# Peripheral.net
KiCad netlist of a schematic drawn in Altium Designer
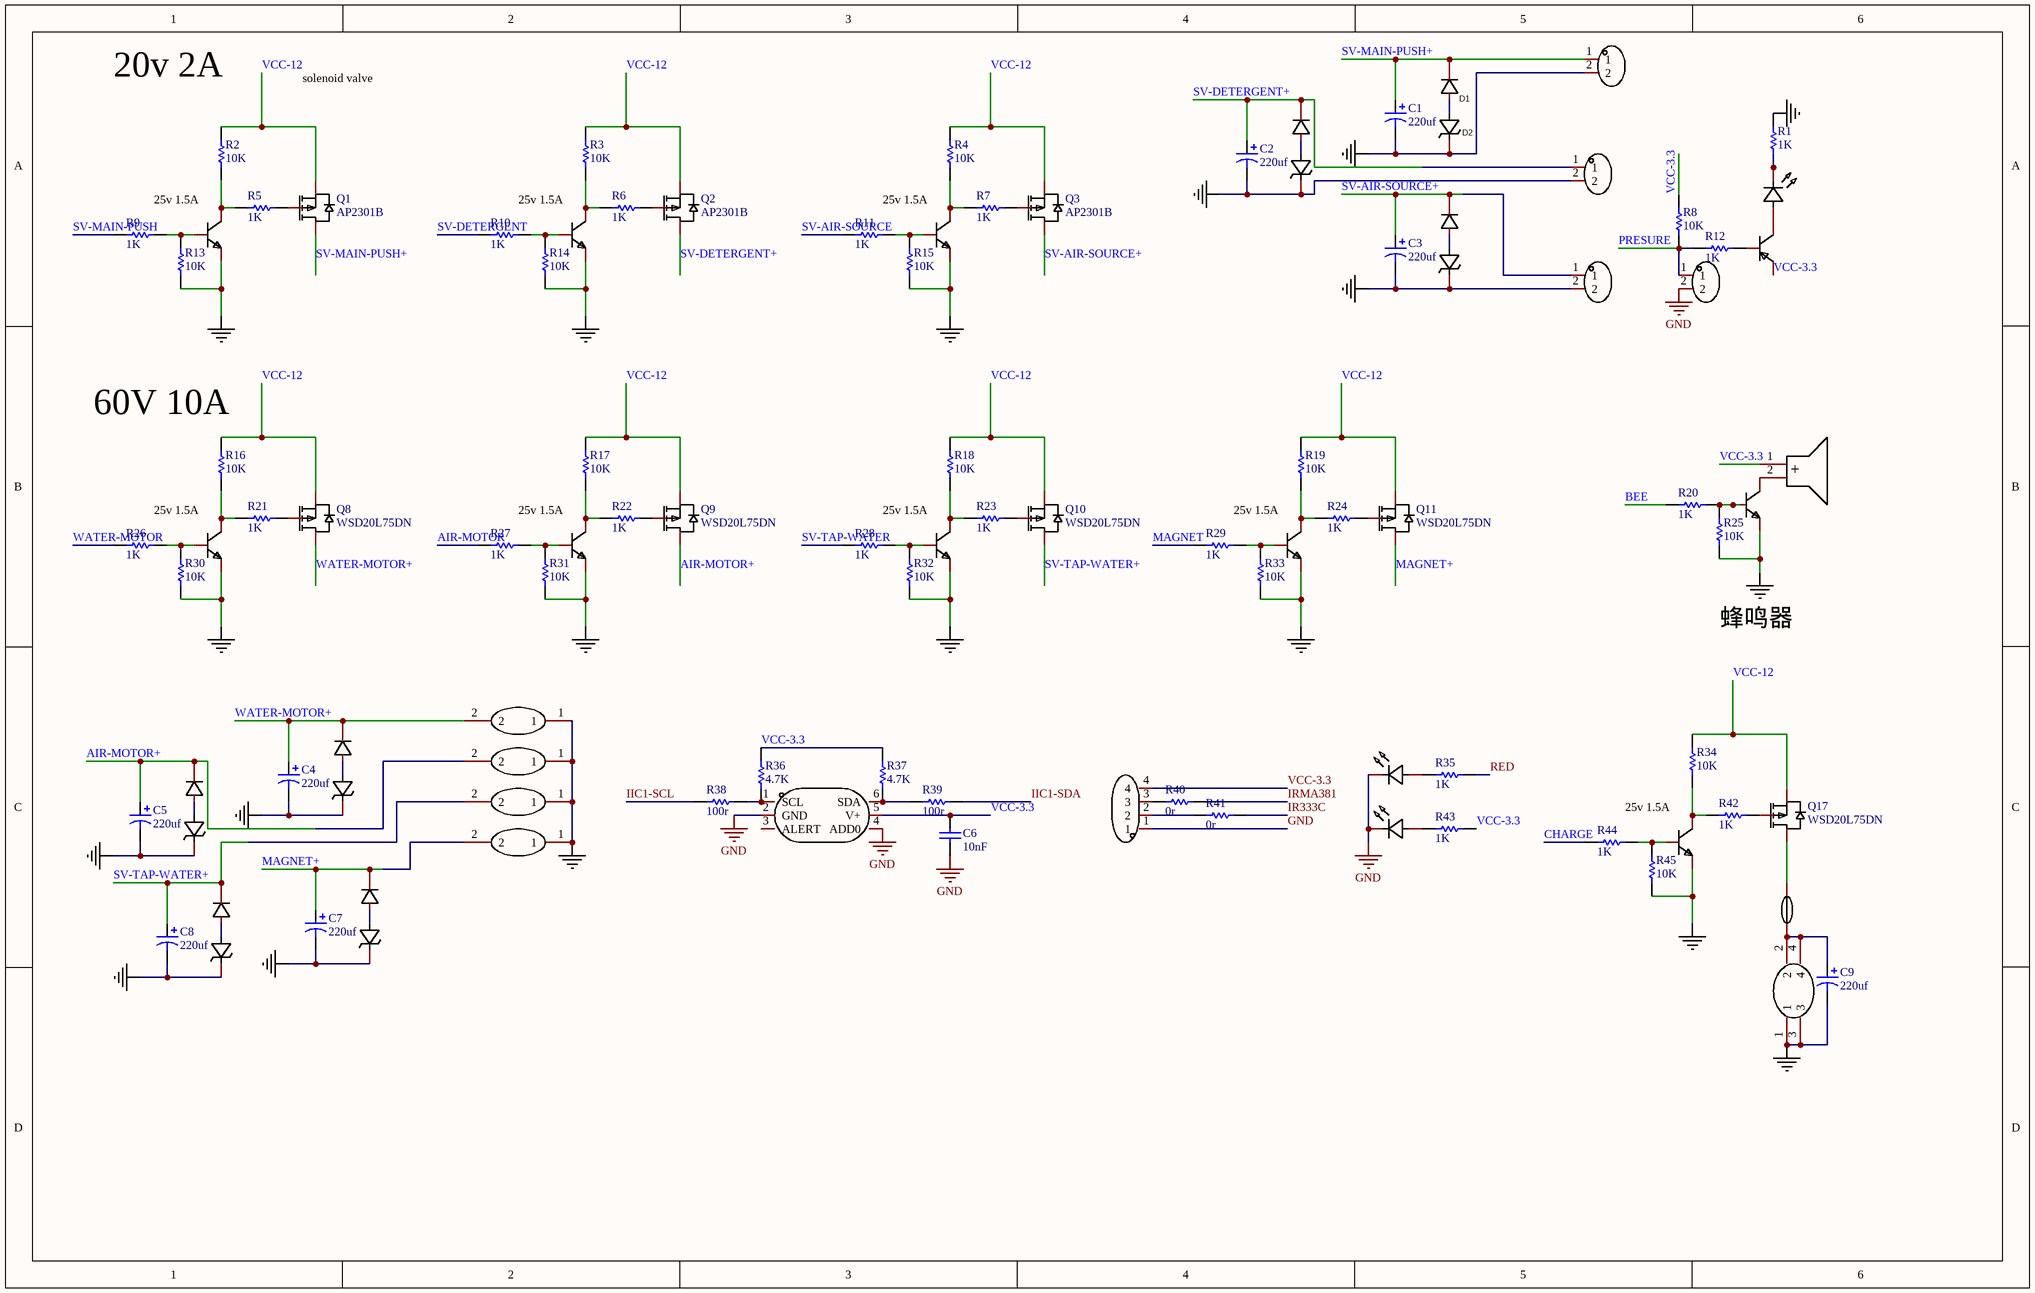
[diagram p0: Peripheral.SchDoc]

(export (version "E")
  (design (tool "Eeschema 10.0.6"))
  (components
    (comp (ref "B1")
      (value "HNB09A03")
      (footprint "BUZ-TH_BD9.0-P5.00-D0.6-FD")
      (fields (field (name "MANUFACTURER") "华能"))
      (libsource (lib "zq") (part "蜂鸣器（有源）"))
    )
    (comp (ref "C1")
      (value "220uf")
      (footprint "zq:CAP-SMD_BD6.3-L6.6-W6.6-LS7.4-FD")
      (description "Polarized Capacitor (Axial)")
      (fields (field (name "Comment") "RVT1E221M0607") (field (name "PUBLISHER") "Altium Limited"))
      (libsource (lib "zq") (part "Cap电解电容"))
    )
    (comp (ref "C2")
      (value "220uf")
      (footprint "zq:CAP-SMD_BD6.3-L6.6-W6.6-LS7.4-FD")
      (description "Polarized Capacitor (Axial)")
      (fields (field (name "Comment") "RVT1E221M0607") (field (name "PUBLISHER") "Altium Limited"))
      (libsource (lib "zq") (part "Cap电解电容"))
    )
    (comp (ref "C3")
      (value "220uf")
      (footprint "zq:CAP-SMD_BD6.3-L6.6-W6.6-LS7.4-FD")
      (description "Polarized Capacitor (Axial)")
      (fields (field (name "Comment") "RVT1E221M0607") (field (name "PUBLISHER") "Altium Limited"))
      (libsource (lib "zq") (part "Cap电解电容"))
    )
    (comp (ref "C4")
      (value "220uf")
      (footprint "zq:CAP-SMD_BD6.3-L6.6-W6.6-LS7.4-FD")
      (description "Polarized Capacitor (Axial)")
      (fields (field (name "Comment") "RVT1E221M0607") (field (name "PUBLISHER") "Altium Limited"))
      (libsource (lib "zq") (part "Cap电解电容"))
    )
    (comp (ref "C5")
      (value "220uf")
      (footprint "zq:CAP-SMD_BD6.3-L6.6-W6.6-LS7.4-FD")
      (description "Polarized Capacitor (Axial)")
      (fields (field (name "Comment") "RVT1E221M0607") (field (name "PUBLISHER") "Altium Limited"))
      (libsource (lib "zq") (part "Cap电解电容"))
    )
    (comp (ref "C6")
      (value "10nF")
      (footprint "zq:C0402")
      (description "Capacitor")
      (fields (field (name "Comment") "CL05B103KB5NNNC") (field (name "PUBLISHER") "Altium Limited"))
      (libsource (lib "zq") (part "10nf"))
    )
    (comp (ref "C7")
      (value "220uf")
      (footprint "zq:CAP-SMD_BD6.3-L6.6-W6.6-LS7.4-FD")
      (description "Polarized Capacitor (Axial)")
      (fields (field (name "Comment") "RVT1E221M0607") (field (name "PUBLISHER") "Altium Limited"))
      (libsource (lib "zq") (part "Cap电解电容"))
    )
    (comp (ref "C8")
      (value "220uf")
      (footprint "zq:CAP-SMD_BD6.3-L6.6-W6.6-LS7.4-FD")
      (description "Polarized Capacitor (Axial)")
      (fields (field (name "Comment") "RVT1E221M0607") (field (name "PUBLISHER") "Altium Limited"))
      (libsource (lib "zq") (part "Cap电解电容"))
    )
    (comp (ref "C9")
      (value "220uf")
      (footprint "zq:CAP-SMD_BD6.3-L6.6-W6.6-LS7.4-FD")
      (description "Polarized Capacitor (Axial)")
      (fields (field (name "Comment") "RVT1E221M0607") (field (name "PUBLISHER") "Altium Limited"))
      (libsource (lib "zq") (part "Cap电解电容"))
    )
    (comp (ref "D1")
      (value "SM4007PL")
      (footprint "zq:SOD-123F_L2.8-W1.8-LS3.7-RD")
      (description "普通二极管 1kv1A")
      (fields (field (name "MANUFACTURER") "MDD(辰达半导体)"))
      (libsource (lib "zq") (part "Diode ordinary"))
    )
    (comp (ref "D2")
      (value "BZT52C18W")
      (footprint "SOD-123_L2.7-W1.6-LS3.8-RD")
      (description "稳压二极管18v 5mA（击穿以后还能恢复）")
      (fields (field (name "MANUFACTURER") "CBI(创基)"))
      (libsource (lib "zq") (part "Diode 18v Zener"))
    )
    (comp (ref "D3")
      (value "SM4007PL")
      (footprint "zq:SOD-123F_L2.8-W1.8-LS3.7-RD")
      (description "普通二极管 1kv1A")
      (fields (field (name "MANUFACTURER") "MDD(辰达半导体)"))
      (libsource (lib "zq") (part "Diode ordinary"))
    )
    (comp (ref "D4")
      (value "BZT52C18W")
      (footprint "SOD-123_L2.7-W1.6-LS3.8-RD")
      (description "稳压二极管18v 5mA（击穿以后还能恢复）")
      (fields (field (name "MANUFACTURER") "CBI(创基)"))
      (libsource (lib "zq") (part "Diode 18v Zener"))
    )
    (comp (ref "D5")
      (value "SM4007PL")
      (footprint "zq:SOD-123F_L2.8-W1.8-LS3.7-RD")
      (description "普通二极管 1kv1A")
      (fields (field (name "MANUFACTURER") "MDD(辰达半导体)"))
      (libsource (lib "zq") (part "Diode ordinary"))
    )
    (comp (ref "D6")
      (value "BZT52C18W")
      (footprint "SOD-123_L2.7-W1.6-LS3.8-RD")
      (description "稳压二极管18v 5mA（击穿以后还能恢复）")
      (fields (field (name "MANUFACTURER") "CBI(创基)"))
      (libsource (lib "zq") (part "Diode 18v Zener"))
    )
    (comp (ref "D7")
      (value "SM4007PL")
      (footprint "zq:SOD-123F_L2.8-W1.8-LS3.7-RD")
      (description "普通二极管 1kv1A")
      (fields (field (name "MANUFACTURER") "MDD(辰达半导体)"))
      (libsource (lib "zq") (part "Diode ordinary"))
    )
    (comp (ref "D8")
      (value "BZT52C18W")
      (footprint "SOD-123_L2.7-W1.6-LS3.8-RD")
      (description "稳压二极管18v 5mA（击穿以后还能恢复）")
      (fields (field (name "MANUFACTURER") "CBI(创基)"))
      (libsource (lib "zq") (part "Diode 18v Zener"))
    )
    (comp (ref "D9")
      (value "KT-0603R")
      (footprint "LED0603-RD_RED")
      (description "红 0603 2.3v")
      (fields
        (field (name "MANUFACTURER") "XINGLIGHT(成兴光)")
        (field (name "MANUFACTURER PART") "XL-1608SURC-06")
      )
      (libsource (lib "zq") (part "led_R"))
    )
    (comp (ref "D10")
      (value "SM4007PL")
      (footprint "zq:SOD-123F_L2.8-W1.8-LS3.7-RD")
      (description "普通二极管 1kv1A")
      (fields (field (name "MANUFACTURER") "MDD(辰达半导体)"))
      (libsource (lib "zq") (part "Diode ordinary"))
    )
    (comp (ref "D11")
      (value "BZT52C18W")
      (footprint "SOD-123_L2.7-W1.6-LS3.8-RD")
      (description "稳压二极管18v 5mA（击穿以后还能恢复）")
      (fields (field (name "MANUFACTURER") "CBI(创基)"))
      (libsource (lib "zq") (part "Diode 18v Zener"))
    )
    (comp (ref "D12")
      (value "KT-0603W")
      (footprint "LED0603-RD_RED")
      (description "白 0603 2.3v")
      (fields
        (field (name "MANUFACTURER") "XINGLIGHT(成兴光)")
        (field (name "MANUFACTURER PART") "XL-1608SURC-06")
      )
      (libsource (lib "zq") (part "led_w"))
    )
    (comp (ref "D13")
      (value "SM4007PL")
      (footprint "zq:SOD-123F_L2.8-W1.8-LS3.7-RD")
      (description "普通二极管 1kv1A")
      (fields (field (name "MANUFACTURER") "MDD(辰达半导体)"))
      (libsource (lib "zq") (part "Diode ordinary"))
    )
    (comp (ref "D14")
      (value "SM4007PL")
      (footprint "zq:SOD-123F_L2.8-W1.8-LS3.7-RD")
      (description "普通二极管 1kv1A")
      (fields (field (name "MANUFACTURER") "MDD(辰达半导体)"))
      (libsource (lib "zq") (part "Diode ordinary"))
    )
    (comp (ref "D15")
      (value "BZT52C18W")
      (footprint "SOD-123_L2.7-W1.6-LS3.8-RD")
      (description "稳压二极管18v 5mA（击穿以后还能恢复）")
      (fields (field (name "MANUFACTURER") "CBI(创基)"))
      (libsource (lib "zq") (part "Diode 18v Zener"))
    )
    (comp (ref "D16")
      (value "BZT52C18W")
      (footprint "SOD-123_L2.7-W1.6-LS3.8-RD")
      (description "稳压二极管18v 5mA（击穿以后还能恢复）")
      (fields (field (name "MANUFACTURER") "CBI(创基)"))
      (libsource (lib "zq") (part "Diode 18v Zener"))
    )
    (comp (ref "F1")
      (value "BSMD2920-600-16V")
      (footprint "F2920")
      (description "自恢复保险丝 6A 16V")
      (fields (field (name "MANUFACTURER") "BHFUSE(佰宏)"))
      (libsource (lib "zq") (part "保险丝"))
    )
    (comp (ref "LED1")
      (value "19-213/Y2C-CQ2R2L/3T(CY)")
      (footprint "LED0603-RD_RED")
      (description "黄 0603 2.3v")
      (fields
        (field (name "MANUFACTURER") "XINGLIGHT(成兴光)")
        (field (name "MANUFACTURER PART") "XL-1608SURC-06")
      )
      (libsource (lib "zq") (part "led_y"))
    )
    (comp (ref "P1")
      (value "ZX-HY2.0-2PZZ")
      (footprint "zq:CONN-TH_2P-P2.00_ZX-HY2.0-2PZZ")
      (description "2p")
      (fields (field (name "MANUFACTURER") "Megastar(兆星)"))
      (libsource (lib "zq") (part "HY2.0-2PZZ"))
    )
    (comp (ref "P2")
      (value "ZX-HY2.0-2PZZ")
      (footprint "zq:CONN-TH_2P-P2.00_ZX-HY2.0-2PZZ")
      (description "2p")
      (fields (field (name "MANUFACTURER") "Megastar(兆星)"))
      (libsource (lib "zq") (part "HY2.0-2PZZ"))
    )
    (comp (ref "P3")
      (value "ZX-HY2.0-2PZZ")
      (footprint "zq:CONN-TH_2P-P2.00_ZX-HY2.0-2PZZ")
      (description "2p")
      (fields (field (name "MANUFACTURER") "Megastar(兆星)"))
      (libsource (lib "zq") (part "HY2.0-2PZZ"))
    )
    (comp (ref "P4")
      (value "ZX-HY2.0-2PZZ")
      (footprint "zq:CONN-TH_2P-P2.00_ZX-HY2.0-2PZZ")
      (description "2p")
      (fields (field (name "MANUFACTURER") "Megastar(兆星)"))
      (libsource (lib "zq") (part "HY2.0-2PZZ"))
    )
    (comp (ref "P5")
      (value "HC-5557-2*1A")
      (footprint "zq:CONN-TH_HAA420A-2A")
      (description "2p")
      (fields (field (name "MANUFACTURER") "HCTL(华灿天禄)"))
      (libsource (lib "zq") (part "HC-5557-2*1A"))
    )
    (comp (ref "P6")
      (value "HC-5557-2*1A")
      (footprint "zq:CONN-TH_HAA420A-2A")
      (description "2p")
      (fields (field (name "MANUFACTURER") "HCTL(华灿天禄)"))
      (libsource (lib "zq") (part "HC-5557-2*1A"))
    )
    (comp (ref "P7")
      (value "HC-5557-2*1A")
      (footprint "zq:CONN-TH_HAA420A-2A")
      (description "2p")
      (fields (field (name "MANUFACTURER") "HCTL(华灿天禄)"))
      (libsource (lib "zq") (part "HC-5557-2*1A"))
    )
    (comp (ref "P8")
      (value "ZX-HY2.0-4PZZ")
      (footprint "zq:CONN-TH_4P-P2.00_HX20020-4A_2")
      (description "4p")
      (fields (field (name "MANUFACTURER") "Megastar(兆星)"))
      (libsource (lib "zq") (part "HY2.0-4PZZ"))
    )
    (comp (ref "P9")
      (value "HC-5557-2*1A")
      (footprint "zq:CONN-TH_HAA420A-2A")
      (description "2p")
      (fields (field (name "MANUFACTURER") "HCTL(华灿天禄)"))
      (libsource (lib "zq") (part "HC-5557-2*1A"))
    )
    (comp (ref "P10")
      (value "HC-5557-2*2A")
      (footprint "zq:CONN-TH_HAA420A-4A")
      (description "4p")
      (fields (field (name "MANUFACTURER") "HCTL(华灿天禄)"))
      (libsource (lib "zq") (part "HC-5557-2*2A"))
    )
    (comp (ref "Q1")
      (value "AP2301B")
      (footprint "zq:SOT-23-3_L2.9-W1.3-P1.90-LS2.4-TR")
      (description "20V 2A")
      (fields (field (name "MANUFACTURER") "ALLPOWER(铨力)") (field (name "NAME") "AP2301B"))
      (libsource (lib "zq") (part "NPN_MOS"))
    )
    (comp (ref "Q2")
      (value "AP2301B")
      (footprint "zq:SOT-23-3_L2.9-W1.3-P1.90-LS2.4-TR")
      (description "20V 2A")
      (fields (field (name "MANUFACTURER") "ALLPOWER(铨力)") (field (name "NAME") "AP2301B"))
      (libsource (lib "zq") (part "NPN_MOS"))
    )
    (comp (ref "Q3")
      (value "AP2301B")
      (footprint "zq:SOT-23-3_L2.9-W1.3-P1.90-LS2.4-TR")
      (description "20V 2A")
      (fields (field (name "MANUFACTURER") "ALLPOWER(铨力)") (field (name "NAME") "AP2301B"))
      (libsource (lib "zq") (part "NPN_MOS"))
    )
    (comp (ref "Q4")
      (value "SS8050(RANGE:200-350)")
      (footprint "zq:SOT-23_L2.9-W1.3-P1.90-LS2.4-BR")
      (description "NPN三极管 高电平导通")
      (fields (field (name "MANUFACTURER") "Nexperia(安世)") (field (name "MANUFACTURER PART") "PMBT3904,215"))
      (libsource (lib "zq") (part "npn_triode"))
    )
    (comp (ref "Q5")
      (value "SS8050(RANGE:200-350)")
      (footprint "zq:SOT-23_L2.9-W1.3-P1.90-LS2.4-BR")
      (description "NPN三极管 高电平导通")
      (fields (field (name "MANUFACTURER") "Nexperia(安世)") (field (name "MANUFACTURER PART") "PMBT3904,215"))
      (libsource (lib "zq") (part "npn_triode"))
    )
    (comp (ref "Q6")
      (value "SS8050(RANGE:200-350)")
      (footprint "zq:SOT-23_L2.9-W1.3-P1.90-LS2.4-BR")
      (description "NPN三极管 高电平导通")
      (fields (field (name "MANUFACTURER") "Nexperia(安世)") (field (name "MANUFACTURER PART") "PMBT3904,215"))
      (libsource (lib "zq") (part "npn_triode"))
    )
    (comp (ref "Q7")
      (value "SS8550 Y2(RANGE:200-350)")
      (footprint "zq:SOT-23_L2.9-W1.3-P1.90-LS2.4-BR")
      (description "PNP三极管 低电平导通")
      (fields (field (name "MANUFACTURER") "CJ(江苏长电/长晶)") (field (name "MANUFACTURER PART") "SS8550 Y2"))
      (libsource (lib "zq") (part "pnp_triode"))
    )
    (comp (ref "Q8")
      (value "WSD20L75DN")
      (footprint "zq:DFN-8_L3.3-W3.3-P0.65-BL_WSD20L75DN")
      (description "20V 2A")
      (fields
        (field (name "MANUFACTURER") "ALLPOWER(铨力)")
        (field (name "MANUFACTURER PART") "AP2301B")
        (field (name "NAME") "WSD20L75DN")
      )
      (libsource (lib "zq") (part "NPN_MOS"))
    )
    (comp (ref "Q9")
      (value "WSD20L75DN")
      (footprint "zq:DFN-8_L3.3-W3.3-P0.65-BL_WSD20L75DN")
      (description "20V 2A")
      (fields
        (field (name "MANUFACTURER") "ALLPOWER(铨力)")
        (field (name "MANUFACTURER PART") "AP2301B")
        (field (name "NAME") "WSD20L75DN")
      )
      (libsource (lib "zq") (part "NPN_MOS"))
    )
    (comp (ref "Q10")
      (value "WSD20L75DN")
      (footprint "zq:DFN-8_L3.3-W3.3-P0.65-BL_WSD20L75DN")
      (description "20V 2A")
      (fields
        (field (name "MANUFACTURER") "ALLPOWER(铨力)")
        (field (name "MANUFACTURER PART") "AP2301B")
        (field (name "NAME") "WSD20L75DN")
      )
      (libsource (lib "zq") (part "NPN_MOS"))
    )
    (comp (ref "Q11")
      (value "WSD20L75DN")
      (footprint "zq:DFN-8_L3.3-W3.3-P0.65-BL_WSD20L75DN")
      (description "20V 2A")
      (fields
        (field (name "MANUFACTURER") "ALLPOWER(铨力)")
        (field (name "MANUFACTURER PART") "AP2301B")
        (field (name "NAME") "WSD20L75DN")
      )
      (libsource (lib "zq") (part "NPN_MOS"))
    )
    (comp (ref "Q12")
      (value "SS8050(RANGE:200-350)")
      (footprint "zq:SOT-23_L2.9-W1.3-P1.90-LS2.4-BR")
      (description "NPN三极管 高电平导通")
      (fields (field (name "MANUFACTURER") "Nexperia(安世)") (field (name "MANUFACTURER PART") "PMBT3904,215"))
      (libsource (lib "zq") (part "npn_triode"))
    )
    (comp (ref "Q13")
      (value "SS8050(RANGE:200-350)")
      (footprint "zq:SOT-23_L2.9-W1.3-P1.90-LS2.4-BR")
      (description "NPN三极管 高电平导通")
      (fields (field (name "MANUFACTURER") "Nexperia(安世)") (field (name "MANUFACTURER PART") "PMBT3904,215"))
      (libsource (lib "zq") (part "npn_triode"))
    )
    (comp (ref "Q14")
      (value "SS8050(RANGE:200-350)")
      (footprint "zq:SOT-23_L2.9-W1.3-P1.90-LS2.4-BR")
      (description "NPN三极管 高电平导通")
      (fields (field (name "MANUFACTURER") "Nexperia(安世)") (field (name "MANUFACTURER PART") "PMBT3904,215"))
      (libsource (lib "zq") (part "npn_triode"))
    )
    (comp (ref "Q15")
      (value "SS8050(RANGE:200-350)")
      (footprint "zq:SOT-23_L2.9-W1.3-P1.90-LS2.4-BR")
      (description "NPN三极管 高电平导通")
      (fields (field (name "MANUFACTURER") "Nexperia(安世)") (field (name "MANUFACTURER PART") "PMBT3904,215"))
      (libsource (lib "zq") (part "npn_triode"))
    )
    (comp (ref "Q16")
      (value "SS8050(RANGE:200-350)")
      (footprint "zq:SOT-23_L2.9-W1.3-P1.90-LS2.4-BR")
      (description "NPN三极管 高电平导通")
      (fields (field (name "MANUFACTURER") "Nexperia(安世)") (field (name "MANUFACTURER PART") "PMBT3904,215"))
      (libsource (lib "zq") (part "npn_triode"))
    )
    (comp (ref "Q17")
      (value "WSD20L75DN")
      (footprint "zq:DFN-8_L3.3-W3.3-P0.65-BL_WSD20L75DN")
      (description "20V 2A")
      (fields
        (field (name "MANUFACTURER") "ALLPOWER(铨力)")
        (field (name "MANUFACTURER PART") "AP2301B")
        (field (name "NAME") "WSD20L75DN")
      )
      (libsource (lib "zq") (part "NPN_MOS"))
    )
    (comp (ref "Q18")
      (value "SS8050(RANGE:200-350)")
      (footprint "zq:SOT-23_L2.9-W1.3-P1.90-LS2.4-BR")
      (description "NPN三极管 高电平导通")
      (fields (field (name "MANUFACTURER") "Nexperia(安世)") (field (name "MANUFACTURER PART") "PMBT3904,215"))
      (libsource (lib "zq") (part "npn_triode"))
    )
    (comp (ref "R1")
      (value "1K")
      (footprint "zq:R0402")
      (description "Semiconductor Resistor")
      (fields (field (name "Comment") "0402WGF1001TCE") (field (name "PUBLISHER") "Altium Limited"))
      (libsource (lib "zq") (part "1k"))
    )
    (comp (ref "R2")
      (value "10K")
      (footprint "zq:R0402")
      (description "Semiconductor Resistor")
      (fields (field (name "Comment") "0402WGF1002TCE") (field (name "PUBLISHER") "Altium Limited"))
      (libsource (lib "zq") (part "10K"))
    )
    (comp (ref "R3")
      (value "10K")
      (footprint "zq:R0402")
      (description "Semiconductor Resistor")
      (fields (field (name "Comment") "0402WGF1002TCE") (field (name "PUBLISHER") "Altium Limited"))
      (libsource (lib "zq") (part "10K"))
    )
    (comp (ref "R4")
      (value "10K")
      (footprint "zq:R0402")
      (description "Semiconductor Resistor")
      (fields (field (name "Comment") "0402WGF1002TCE") (field (name "PUBLISHER") "Altium Limited"))
      (libsource (lib "zq") (part "10K"))
    )
    (comp (ref "R5")
      (value "1K")
      (footprint "zq:R0402")
      (description "Semiconductor Resistor")
      (fields (field (name "Comment") "0402WGF1001TCE") (field (name "PUBLISHER") "Altium Limited"))
      (libsource (lib "zq") (part "1k"))
    )
    (comp (ref "R6")
      (value "1K")
      (footprint "zq:R0402")
      (description "Semiconductor Resistor")
      (fields (field (name "Comment") "0402WGF1001TCE") (field (name "PUBLISHER") "Altium Limited"))
      (libsource (lib "zq") (part "1k"))
    )
    (comp (ref "R7")
      (value "1K")
      (footprint "zq:R0402")
      (description "Semiconductor Resistor")
      (fields (field (name "Comment") "0402WGF1001TCE") (field (name "PUBLISHER") "Altium Limited"))
      (libsource (lib "zq") (part "1k"))
    )
    (comp (ref "R8")
      (value "10K")
      (footprint "zq:R0402")
      (description "Semiconductor Resistor")
      (fields (field (name "Comment") "0402WGF1002TCE") (field (name "PUBLISHER") "Altium Limited"))
      (libsource (lib "zq") (part "10K"))
    )
    (comp (ref "R9")
      (value "1K")
      (footprint "zq:R0402")
      (description "Semiconductor Resistor")
      (fields (field (name "Comment") "0402WGF1001TCE") (field (name "PUBLISHER") "Altium Limited"))
      (libsource (lib "zq") (part "1k"))
    )
    (comp (ref "R10")
      (value "1K")
      (footprint "zq:R0402")
      (description "Semiconductor Resistor")
      (fields (field (name "Comment") "0402WGF1001TCE") (field (name "PUBLISHER") "Altium Limited"))
      (libsource (lib "zq") (part "1k"))
    )
    (comp (ref "R11")
      (value "1K")
      (footprint "zq:R0402")
      (description "Semiconductor Resistor")
      (fields (field (name "Comment") "0402WGF1001TCE") (field (name "PUBLISHER") "Altium Limited"))
      (libsource (lib "zq") (part "1k"))
    )
    (comp (ref "R12")
      (value "1K")
      (footprint "zq:R0402")
      (description "Semiconductor Resistor")
      (fields (field (name "Comment") "0402WGF1001TCE") (field (name "PUBLISHER") "Altium Limited"))
      (libsource (lib "zq") (part "1k"))
    )
    (comp (ref "R13")
      (value "10K")
      (footprint "zq:R0402")
      (description "Semiconductor Resistor")
      (fields (field (name "Comment") "0402WGF1002TCE") (field (name "PUBLISHER") "Altium Limited"))
      (libsource (lib "zq") (part "10K"))
    )
    (comp (ref "R14")
      (value "10K")
      (footprint "zq:R0402")
      (description "Semiconductor Resistor")
      (fields (field (name "Comment") "0402WGF1002TCE") (field (name "PUBLISHER") "Altium Limited"))
      (libsource (lib "zq") (part "10K"))
    )
    (comp (ref "R15")
      (value "10K")
      (footprint "zq:R0402")
      (description "Semiconductor Resistor")
      (fields (field (name "Comment") "0402WGF1002TCE") (field (name "PUBLISHER") "Altium Limited"))
      (libsource (lib "zq") (part "10K"))
    )
    (comp (ref "R16")
      (value "10K")
      (footprint "zq:R0402")
      (description "Semiconductor Resistor")
      (fields (field (name "Comment") "0402WGF1002TCE") (field (name "PUBLISHER") "Altium Limited"))
      (libsource (lib "zq") (part "10K"))
    )
    (comp (ref "R17")
      (value "10K")
      (footprint "zq:R0402")
      (description "Semiconductor Resistor")
      (fields (field (name "Comment") "0402WGF1002TCE") (field (name "PUBLISHER") "Altium Limited"))
      (libsource (lib "zq") (part "10K"))
    )
    (comp (ref "R18")
      (value "10K")
      (footprint "zq:R0402")
      (description "Semiconductor Resistor")
      (fields (field (name "Comment") "0402WGF1002TCE") (field (name "PUBLISHER") "Altium Limited"))
      (libsource (lib "zq") (part "10K"))
    )
    (comp (ref "R19")
      (value "10K")
      (footprint "zq:R0402")
      (description "Semiconductor Resistor")
      (fields (field (name "Comment") "0402WGF1002TCE") (field (name "PUBLISHER") "Altium Limited"))
      (libsource (lib "zq") (part "10K"))
    )
    (comp (ref "R20")
      (value "1K")
      (footprint "zq:R0402")
      (description "Semiconductor Resistor")
      (fields (field (name "Comment") "0402WGF1001TCE") (field (name "PUBLISHER") "Altium Limited"))
      (libsource (lib "zq") (part "1k"))
    )
    (comp (ref "R21")
      (value "1K")
      (footprint "zq:R0402")
      (description "Semiconductor Resistor")
      (fields (field (name "Comment") "0402WGF1001TCE") (field (name "PUBLISHER") "Altium Limited"))
      (libsource (lib "zq") (part "1k"))
    )
    (comp (ref "R22")
      (value "1K")
      (footprint "zq:R0402")
      (description "Semiconductor Resistor")
      (fields (field (name "Comment") "0402WGF1001TCE") (field (name "PUBLISHER") "Altium Limited"))
      (libsource (lib "zq") (part "1k"))
    )
    (comp (ref "R23")
      (value "1K")
      (footprint "zq:R0402")
      (description "Semiconductor Resistor")
      (fields (field (name "Comment") "0402WGF1001TCE") (field (name "PUBLISHER") "Altium Limited"))
      (libsource (lib "zq") (part "1k"))
    )
    (comp (ref "R24")
      (value "1K")
      (footprint "zq:R0402")
      (description "Semiconductor Resistor")
      (fields (field (name "Comment") "0402WGF1001TCE") (field (name "PUBLISHER") "Altium Limited"))
      (libsource (lib "zq") (part "1k"))
    )
    (comp (ref "R25")
      (value "10K")
      (footprint "zq:R0402")
      (description "Semiconductor Resistor")
      (fields (field (name "Comment") "0402WGF1002TCE") (field (name "PUBLISHER") "Altium Limited"))
      (libsource (lib "zq") (part "10K"))
    )
    (comp (ref "R26")
      (value "1K")
      (footprint "zq:R0402")
      (description "Semiconductor Resistor")
      (fields (field (name "Comment") "0402WGF1001TCE") (field (name "PUBLISHER") "Altium Limited"))
      (libsource (lib "zq") (part "1k"))
    )
    (comp (ref "R27")
      (value "1K")
      (footprint "zq:R0402")
      (description "Semiconductor Resistor")
      (fields (field (name "Comment") "0402WGF1001TCE") (field (name "PUBLISHER") "Altium Limited"))
      (libsource (lib "zq") (part "1k"))
    )
    (comp (ref "R28")
      (value "1K")
      (footprint "zq:R0402")
      (description "Semiconductor Resistor")
      (fields (field (name "Comment") "0402WGF1001TCE") (field (name "PUBLISHER") "Altium Limited"))
      (libsource (lib "zq") (part "1k"))
    )
    (comp (ref "R29")
      (value "1K")
      (footprint "zq:R0402")
      (description "Semiconductor Resistor")
      (fields (field (name "Comment") "0402WGF1001TCE") (field (name "PUBLISHER") "Altium Limited"))
      (libsource (lib "zq") (part "1k"))
    )
    (comp (ref "R30")
      (value "10K")
      (footprint "zq:R0402")
      (description "Semiconductor Resistor")
      (fields (field (name "Comment") "0402WGF1002TCE") (field (name "PUBLISHER") "Altium Limited"))
      (libsource (lib "zq") (part "10K"))
    )
    (comp (ref "R31")
      (value "10K")
      (footprint "zq:R0402")
      (description "Semiconductor Resistor")
      (fields (field (name "Comment") "0402WGF1002TCE") (field (name "PUBLISHER") "Altium Limited"))
      (libsource (lib "zq") (part "10K"))
    )
    (comp (ref "R32")
      (value "10K")
      (footprint "zq:R0402")
      (description "Semiconductor Resistor")
      (fields (field (name "Comment") "0402WGF1002TCE") (field (name "PUBLISHER") "Altium Limited"))
      (libsource (lib "zq") (part "10K"))
    )
    (comp (ref "R33")
      (value "10K")
      (footprint "zq:R0402")
      (description "Semiconductor Resistor")
      (fields (field (name "Comment") "0402WGF1002TCE") (field (name "PUBLISHER") "Altium Limited"))
      (libsource (lib "zq") (part "10K"))
    )
    (comp (ref "R34")
      (value "10K")
      (footprint "zq:R0402")
      (description "Semiconductor Resistor")
      (fields (field (name "Comment") "0402WGF1002TCE") (field (name "PUBLISHER") "Altium Limited"))
      (libsource (lib "zq") (part "10K"))
    )
    (comp (ref "R35")
      (value "1K")
      (footprint "zq:R0402")
      (description "Semiconductor Resistor")
      (fields (field (name "Comment") "0402WGF1001TCE") (field (name "PUBLISHER") "Altium Limited"))
      (libsource (lib "zq") (part "1k"))
    )
    (comp (ref "R36")
      (value "4.7K")
      (footprint "zq:R0402")
      (description "Semiconductor Resistor")
      (fields (field (name "Comment") "0402WGF4701TCE") (field (name "PUBLISHER") "Altium Limited"))
      (libsource (lib "zq") (part "4.7k"))
    )
    (comp (ref "R37")
      (value "4.7K")
      (footprint "zq:R0402")
      (description "Semiconductor Resistor")
      (fields (field (name "Comment") "0402WGF4701TCE") (field (name "PUBLISHER") "Altium Limited"))
      (libsource (lib "zq") (part "4.7k"))
    )
    (comp (ref "R38")
      (value "100r")
      (footprint "zq:R0402")
      (fields (field (name "Comment") "0402WGF1000TCE") (field (name "PUBLISHER") "Altium Limited"))
      (libsource (lib "zq") (part "100r"))
    )
    (comp (ref "R39")
      (value "100r")
      (footprint "zq:R0402")
      (fields (field (name "Comment") "0402WGF1000TCE") (field (name "PUBLISHER") "Altium Limited"))
      (libsource (lib "zq") (part "100r"))
    )
    (comp (ref "R40")
      (value "0r")
      (footprint "zq:R0402")
      (fields (field (name "Comment") "0402WGF0000TCE") (field (name "PUBLISHER") "Altium Limited"))
      (libsource (lib "zq") (part "0r"))
    )
    (comp (ref "R41")
      (value "0r")
      (footprint "zq:R0402")
      (fields (field (name "Comment") "0402WGF0000TCE") (field (name "PUBLISHER") "Altium Limited"))
      (libsource (lib "zq") (part "0r"))
    )
    (comp (ref "R42")
      (value "1K")
      (footprint "zq:R0402")
      (description "Semiconductor Resistor")
      (fields (field (name "Comment") "0402WGF1001TCE") (field (name "PUBLISHER") "Altium Limited"))
      (libsource (lib "zq") (part "1k"))
    )
    (comp (ref "R43")
      (value "1K")
      (footprint "zq:R0402")
      (description "Semiconductor Resistor")
      (fields (field (name "Comment") "0402WGF1001TCE") (field (name "PUBLISHER") "Altium Limited"))
      (libsource (lib "zq") (part "1k"))
    )
    (comp (ref "R44")
      (value "1K")
      (footprint "zq:R0402")
      (description "Semiconductor Resistor")
      (fields (field (name "Comment") "0402WGF1001TCE") (field (name "PUBLISHER") "Altium Limited"))
      (libsource (lib "zq") (part "1k"))
    )
    (comp (ref "R45")
      (value "10K")
      (footprint "zq:R0402")
      (description "Semiconductor Resistor")
      (fields (field (name "Comment") "0402WGF1002TCE") (field (name "PUBLISHER") "Altium Limited"))
      (libsource (lib "zq") (part "10K"))
    )
    (comp (ref "U1")
      (value "TMP112AIDRLR")
      (footprint "SOT-563_L1.6-W1.2-P0.50-LS1.6-BR")
      (description "温度传感器")
      (fields (field (name "MANUFACTURER") "UMW(友台半导体)"))
      (libsource (lib "zq") (part "TMP112AIDRLR"))
    )
  )
  (nets
    (net (code "1") (name "/AIR-MOTOR") (class "Default")
      (node (ref "R27") (pin "1") (pinfunction "1_1") (pintype "passive"))
    )
    (net (code "2") (name "/AIR-MOTOR+") (class "Default")
      (node (ref "C5") (pin "1") (pinfunction "1_1") (pintype "passive"))
      (node (ref "D10") (pin "1") (pinfunction "C_1") (pintype "passive"))
      (node (ref "P6") (pin "2") (pinfunction "2_2") (pintype "passive"))
      (node (ref "Q9") (pin "3") (pinfunction "D_3") (pintype "passive"))
    )
    (net (code "3") (name "/BEE") (class "Default")
      (node (ref "R20") (pin "1") (pinfunction "1_1") (pintype "passive"))
    )
    (net (code "4") (name "/CHARGE") (class "Default")
      (node (ref "R44") (pin "1") (pinfunction "1_1") (pintype "passive"))
    )
    (net (code "5") (name "/IIC1-SCL") (class "Default")
      (node (ref "R38") (pin "1") (pinfunction "1_1") (pintype "passive"))
    )
    (net (code "6") (name "/IIC1-SDA") (class "Default")
      (node (ref "R39") (pin "2") (pinfunction "2_2") (pintype "passive"))
    )
    (net (code "7") (name "/IR333C") (class "Default")
      (node (ref "R41") (pin "2") (pinfunction "2_2") (pintype "passive"))
    )
    (net (code "8") (name "/IRMA381") (class "Default")
      (node (ref "R40") (pin "2") (pinfunction "2_2") (pintype "passive"))
    )
    (net (code "9") (name "/MAGNET") (class "Default")
      (node (ref "R29") (pin "1") (pinfunction "1_1") (pintype "passive"))
    )
    (net (code "10") (name "/MAGNET+") (class "Default")
      (node (ref "C7") (pin "1") (pinfunction "1_1") (pintype "passive"))
      (node (ref "D13") (pin "1") (pinfunction "C_1") (pintype "passive"))
      (node (ref "P9") (pin "2") (pinfunction "2_2") (pintype "passive"))
      (node (ref "Q11") (pin "3") (pinfunction "D_3") (pintype "passive"))
    )
    (net (code "11") (name "/PRESURE") (class "Default")
      (node (ref "P4") (pin "1") (pinfunction "1_1") (pintype "passive"))
      (node (ref "R12") (pin "2") (pinfunction "2_2") (pintype "passive"))
      (node (ref "R8") (pin "1") (pinfunction "1_1") (pintype "passive"))
    )
    (net (code "12") (name "/RED") (class "Default")
      (node (ref "R35") (pin "2") (pinfunction "2_2") (pintype "passive"))
    )
    (net (code "13") (name "/SV-AIR-SOURCE") (class "Default")
      (node (ref "R11") (pin "1") (pinfunction "1_1") (pintype "passive"))
    )
    (net (code "14") (name "/SV-AIR-SOURCE+") (class "Default")
      (node (ref "C3") (pin "1") (pinfunction "1_1") (pintype "passive"))
      (node (ref "D5") (pin "1") (pinfunction "C_1") (pintype "passive"))
      (node (ref "P3") (pin "1") (pinfunction "1_1") (pintype "passive"))
      (node (ref "Q3") (pin "3") (pinfunction "D_3") (pintype "passive"))
    )
    (net (code "15") (name "/SV-DETERGENT") (class "Default")
      (node (ref "R10") (pin "1") (pinfunction "1_1") (pintype "passive"))
    )
    (net (code "16") (name "/SV-DETERGENT+") (class "Default")
      (node (ref "C2") (pin "1") (pinfunction "1_1") (pintype "passive"))
      (node (ref "D3") (pin "1") (pinfunction "C_1") (pintype "passive"))
      (node (ref "P2") (pin "1") (pinfunction "1_1") (pintype "passive"))
      (node (ref "Q2") (pin "3") (pinfunction "D_3") (pintype "passive"))
    )
    (net (code "17") (name "/SV-MAIN-PUSH") (class "Default")
      (node (ref "R9") (pin "1") (pinfunction "1_1") (pintype "passive"))
    )
    (net (code "18") (name "/SV-MAIN-PUSH+") (class "Default")
      (node (ref "C1") (pin "1") (pinfunction "1_1") (pintype "passive"))
      (node (ref "D1") (pin "1") (pinfunction "C_1") (pintype "passive"))
      (node (ref "P1") (pin "1") (pinfunction "1_1") (pintype "passive"))
      (node (ref "Q1") (pin "3") (pinfunction "D_3") (pintype "passive"))
    )
    (net (code "19") (name "/SV-TAP-WATER") (class "Default")
      (node (ref "R28") (pin "1") (pinfunction "1_1") (pintype "passive"))
    )
    (net (code "20") (name "/SV-TAP-WATER+") (class "Default")
      (node (ref "C8") (pin "1") (pinfunction "1_1") (pintype "passive"))
      (node (ref "D14") (pin "1") (pinfunction "C_1") (pintype "passive"))
      (node (ref "P7") (pin "2") (pinfunction "2_2") (pintype "passive"))
      (node (ref "Q10") (pin "3") (pinfunction "D_3") (pintype "passive"))
    )
    (net (code "21") (name "/VCC-3.3") (class "Default")
      (node (ref "B1") (pin "1") (pinfunction "+_1") (pintype "passive"))
      (node (ref "C6") (pin "1") (pinfunction "1_1") (pintype "passive"))
      (node (ref "P8") (pin "4") (pinfunction "4_4") (pintype "passive"))
      (node (ref "Q7") (pin "2") (pinfunction "E_2") (pintype "passive"))
      (node (ref "R36") (pin "2") (pinfunction "2_2") (pintype "passive"))
      (node (ref "R37") (pin "2") (pinfunction "2_2") (pintype "passive"))
      (node (ref "R43") (pin "2") (pinfunction "2_2") (pintype "passive"))
      (node (ref "R8") (pin "2") (pinfunction "2_2") (pintype "passive"))
      (node (ref "U1") (pin "5") (pinfunction "V+_5") (pintype "passive"))
    )
    (net (code "22") (name "/VCC-12") (class "Default")
      (node (ref "Q1") (pin "1") (pinfunction "S_1") (pintype "passive"))
      (node (ref "Q10") (pin "1") (pinfunction "S_1") (pintype "passive"))
      (node (ref "Q11") (pin "1") (pinfunction "S_1") (pintype "passive"))
      (node (ref "Q17") (pin "1") (pinfunction "S_1") (pintype "passive"))
      (node (ref "Q2") (pin "1") (pinfunction "S_1") (pintype "passive"))
      (node (ref "Q3") (pin "1") (pinfunction "S_1") (pintype "passive"))
      (node (ref "Q8") (pin "1") (pinfunction "S_1") (pintype "passive"))
      (node (ref "Q9") (pin "1") (pinfunction "S_1") (pintype "passive"))
      (node (ref "R16") (pin "2") (pinfunction "2_2") (pintype "passive"))
      (node (ref "R17") (pin "2") (pinfunction "2_2") (pintype "passive"))
      (node (ref "R18") (pin "2") (pinfunction "2_2") (pintype "passive"))
      (node (ref "R19") (pin "2") (pinfunction "2_2") (pintype "passive"))
      (node (ref "R2") (pin "2") (pinfunction "2_2") (pintype "passive"))
      (node (ref "R3") (pin "2") (pinfunction "2_2") (pintype "passive"))
      (node (ref "R34") (pin "2") (pinfunction "2_2") (pintype "passive"))
      (node (ref "R4") (pin "2") (pinfunction "2_2") (pintype "passive"))
    )
    (net (code "23") (name "/WATER-MOTOR") (class "Default")
      (node (ref "R26") (pin "1") (pinfunction "1_1") (pintype "passive"))
    )
    (net (code "24") (name "/WATER-MOTOR+") (class "Default")
      (node (ref "C4") (pin "1") (pinfunction "1_1") (pintype "passive"))
      (node (ref "D7") (pin "1") (pinfunction "C_1") (pintype "passive"))
      (node (ref "P5") (pin "2") (pinfunction "2_2") (pintype "passive"))
      (node (ref "Q8") (pin "3") (pinfunction "D_3") (pintype "passive"))
    )
    (net (code "25") (name "GND") (class "Default")
      (node (ref "C1") (pin "2") (pinfunction "2_2") (pintype "passive"))
      (node (ref "C2") (pin "2") (pinfunction "2_2") (pintype "passive"))
      (node (ref "C3") (pin "2") (pinfunction "2_2") (pintype "passive"))
      (node (ref "C4") (pin "2") (pinfunction "2_2") (pintype "passive"))
      (node (ref "C5") (pin "2") (pinfunction "2_2") (pintype "passive"))
      (node (ref "C6") (pin "2") (pinfunction "2_2") (pintype "passive"))
      (node (ref "C7") (pin "2") (pinfunction "2_2") (pintype "passive"))
      (node (ref "C8") (pin "2") (pinfunction "2_2") (pintype "passive"))
      (node (ref "C9") (pin "2") (pinfunction "2_2") (pintype "passive"))
      (node (ref "D11") (pin "1") (pinfunction "C_1") (pintype "passive"))
      (node (ref "D12") (pin "1") (pinfunction "K_1") (pintype "passive"))
      (node (ref "D15") (pin "1") (pinfunction "C_1") (pintype "passive"))
      (node (ref "D16") (pin "1") (pinfunction "C_1") (pintype "passive"))
      (node (ref "D2") (pin "1") (pinfunction "C_1") (pintype "passive"))
      (node (ref "D4") (pin "1") (pinfunction "C_1") (pintype "passive"))
      (node (ref "D6") (pin "1") (pinfunction "C_1") (pintype "passive"))
      (node (ref "D8") (pin "1") (pinfunction "C_1") (pintype "passive"))
      (node (ref "D9") (pin "1") (pinfunction "K_1") (pintype "passive"))
      (node (ref "P1") (pin "2") (pinfunction "2_2") (pintype "passive"))
      (node (ref "P10") (pin "1") (pinfunction "1_1") (pintype "passive"))
      (node (ref "P10") (pin "3") (pinfunction "3_3") (pintype "passive"))
      (node (ref "P2") (pin "2") (pinfunction "2_2") (pintype "passive"))
      (node (ref "P3") (pin "2") (pinfunction "2_2") (pintype "passive"))
      (node (ref "P4") (pin "2") (pinfunction "2_2") (pintype "passive"))
      (node (ref "P5") (pin "1") (pinfunction "1_1") (pintype "passive"))
      (node (ref "P6") (pin "1") (pinfunction "1_1") (pintype "passive"))
      (node (ref "P7") (pin "1") (pinfunction "1_1") (pintype "passive"))
      (node (ref "P8") (pin "1") (pinfunction "1_1") (pintype "passive"))
      (node (ref "P9") (pin "1") (pinfunction "1_1") (pintype "passive"))
      (node (ref "Q12") (pin "2") (pinfunction "2_2") (pintype "passive"))
      (node (ref "Q13") (pin "2") (pinfunction "2_2") (pintype "passive"))
      (node (ref "Q14") (pin "2") (pinfunction "2_2") (pintype "passive"))
      (node (ref "Q15") (pin "2") (pinfunction "2_2") (pintype "passive"))
      (node (ref "Q16") (pin "2") (pinfunction "2_2") (pintype "passive"))
      (node (ref "Q18") (pin "2") (pinfunction "2_2") (pintype "passive"))
      (node (ref "Q4") (pin "2") (pinfunction "2_2") (pintype "passive"))
      (node (ref "Q5") (pin "2") (pinfunction "2_2") (pintype "passive"))
      (node (ref "Q6") (pin "2") (pinfunction "2_2") (pintype "passive"))
      (node (ref "R1") (pin "2") (pinfunction "2_2") (pintype "passive"))
      (node (ref "R13") (pin "1") (pinfunction "1_1") (pintype "passive"))
      (node (ref "R14") (pin "1") (pinfunction "1_1") (pintype "passive"))
      (node (ref "R15") (pin "1") (pinfunction "1_1") (pintype "passive"))
      (node (ref "R25") (pin "1") (pinfunction "1_1") (pintype "passive"))
      (node (ref "R30") (pin "1") (pinfunction "1_1") (pintype "passive"))
      (node (ref "R31") (pin "1") (pinfunction "1_1") (pintype "passive"))
      (node (ref "R32") (pin "1") (pinfunction "1_1") (pintype "passive"))
      (node (ref "R33") (pin "1") (pinfunction "1_1") (pintype "passive"))
      (node (ref "R45") (pin "1") (pinfunction "1_1") (pintype "passive"))
      (node (ref "U1") (pin "2") (pinfunction "GND_2") (pintype "passive"))
      (node (ref "U1") (pin "4") (pinfunction "ADD0_4") (pintype "passive"))
    )
    (net (code "26") (name "Net-(B1--)") (class "Default")
      (node (ref "B1") (pin "2") (pinfunction "-_2") (pintype "passive"))
      (node (ref "Q12") (pin "3") (pinfunction "3_3") (pintype "passive"))
    )
    (net (code "27") (name "Net-(C9-Pad1)") (class "Default")
      (node (ref "C9") (pin "1") (pinfunction "1_1") (pintype "passive"))
      (node (ref "F1") (pin "1") (pinfunction "1_1") (pintype "passive"))
      (node (ref "P10") (pin "2") (pinfunction "2_2") (pintype "passive"))
      (node (ref "P10") (pin "4") (pinfunction "4_4") (pintype "passive"))
    )
    (net (code "28") (name "Net-(D1-A)") (class "Default")
      (node (ref "D1") (pin "2") (pinfunction "A_2") (pintype "passive"))
      (node (ref "D2") (pin "2") (pinfunction "A_2") (pintype "passive"))
    )
    (net (code "29") (name "Net-(D3-A)") (class "Default")
      (node (ref "D3") (pin "2") (pinfunction "A_2") (pintype "passive"))
      (node (ref "D4") (pin "2") (pinfunction "A_2") (pintype "passive"))
    )
    (net (code "30") (name "Net-(D5-A)") (class "Default")
      (node (ref "D5") (pin "2") (pinfunction "A_2") (pintype "passive"))
      (node (ref "D6") (pin "2") (pinfunction "A_2") (pintype "passive"))
    )
    (net (code "31") (name "Net-(D7-A)") (class "Default")
      (node (ref "D7") (pin "2") (pinfunction "A_2") (pintype "passive"))
      (node (ref "D8") (pin "2") (pinfunction "A_2") (pintype "passive"))
    )
    (net (code "32") (name "Net-(D9-A)") (class "Default")
      (node (ref "D9") (pin "2") (pinfunction "A_2") (pintype "passive"))
      (node (ref "R35") (pin "1") (pinfunction "1_1") (pintype "passive"))
    )
    (net (code "33") (name "Net-(D10-A)") (class "Default")
      (node (ref "D10") (pin "2") (pinfunction "A_2") (pintype "passive"))
      (node (ref "D11") (pin "2") (pinfunction "A_2") (pintype "passive"))
    )
    (net (code "34") (name "Net-(D12-A)") (class "Default")
      (node (ref "D12") (pin "2") (pinfunction "A_2") (pintype "passive"))
      (node (ref "R43") (pin "1") (pinfunction "1_1") (pintype "passive"))
    )
    (net (code "35") (name "Net-(D13-A)") (class "Default")
      (node (ref "D13") (pin "2") (pinfunction "A_2") (pintype "passive"))
      (node (ref "D15") (pin "2") (pinfunction "A_2") (pintype "passive"))
    )
    (net (code "36") (name "Net-(D14-A)") (class "Default")
      (node (ref "D14") (pin "2") (pinfunction "A_2") (pintype "passive"))
      (node (ref "D16") (pin "2") (pinfunction "A_2") (pintype "passive"))
    )
    (net (code "37") (name "Net-(LED1-A)") (class "Default")
      (node (ref "LED1") (pin "2") (pinfunction "A_2") (pintype "passive"))
      (node (ref "Q7") (pin "3") (pinfunction "C_3") (pintype "passive"))
    )
    (net (code "38") (name "Net-(LED1-K)") (class "Default")
      (node (ref "LED1") (pin "1") (pinfunction "K_1") (pintype "passive"))
      (node (ref "R1") (pin "1") (pinfunction "1_1") (pintype "passive"))
    )
    (net (code "39") (name "Net-(P8-Pad2)") (class "Default")
      (node (ref "P8") (pin "2") (pinfunction "2_2") (pintype "passive"))
      (node (ref "R41") (pin "1") (pinfunction "1_1") (pintype "passive"))
    )
    (net (code "40") (name "Net-(P8-Pad3)") (class "Default")
      (node (ref "P8") (pin "3") (pinfunction "3_3") (pintype "passive"))
      (node (ref "R40") (pin "1") (pinfunction "1_1") (pintype "passive"))
    )
    (net (code "41") (name "Net-(Q1-G)") (class "Default")
      (node (ref "Q1") (pin "2") (pinfunction "G_2") (pintype "passive"))
      (node (ref "R5") (pin "2") (pinfunction "2_2") (pintype "passive"))
    )
    (net (code "42") (name "Net-(Q2-G)") (class "Default")
      (node (ref "Q2") (pin "2") (pinfunction "G_2") (pintype "passive"))
      (node (ref "R6") (pin "2") (pinfunction "2_2") (pintype "passive"))
    )
    (net (code "43") (name "Net-(Q3-G)") (class "Default")
      (node (ref "Q3") (pin "2") (pinfunction "G_2") (pintype "passive"))
      (node (ref "R7") (pin "2") (pinfunction "2_2") (pintype "passive"))
    )
    (net (code "44") (name "Net-(Q4-Pad1)") (class "Default")
      (node (ref "Q4") (pin "1") (pinfunction "1_1") (pintype "passive"))
      (node (ref "R13") (pin "2") (pinfunction "2_2") (pintype "passive"))
      (node (ref "R9") (pin "2") (pinfunction "2_2") (pintype "passive"))
    )
    (net (code "45") (name "Net-(Q4-Pad3)") (class "Default")
      (node (ref "Q4") (pin "3") (pinfunction "3_3") (pintype "passive"))
      (node (ref "R2") (pin "1") (pinfunction "1_1") (pintype "passive"))
      (node (ref "R5") (pin "1") (pinfunction "1_1") (pintype "passive"))
    )
    (net (code "46") (name "Net-(Q5-Pad1)") (class "Default")
      (node (ref "Q5") (pin "1") (pinfunction "1_1") (pintype "passive"))
      (node (ref "R10") (pin "2") (pinfunction "2_2") (pintype "passive"))
      (node (ref "R14") (pin "2") (pinfunction "2_2") (pintype "passive"))
    )
    (net (code "47") (name "Net-(Q5-Pad3)") (class "Default")
      (node (ref "Q5") (pin "3") (pinfunction "3_3") (pintype "passive"))
      (node (ref "R3") (pin "1") (pinfunction "1_1") (pintype "passive"))
      (node (ref "R6") (pin "1") (pinfunction "1_1") (pintype "passive"))
    )
    (net (code "48") (name "Net-(Q6-Pad1)") (class "Default")
      (node (ref "Q6") (pin "1") (pinfunction "1_1") (pintype "passive"))
      (node (ref "R11") (pin "2") (pinfunction "2_2") (pintype "passive"))
      (node (ref "R15") (pin "2") (pinfunction "2_2") (pintype "passive"))
    )
    (net (code "49") (name "Net-(Q6-Pad3)") (class "Default")
      (node (ref "Q6") (pin "3") (pinfunction "3_3") (pintype "passive"))
      (node (ref "R4") (pin "1") (pinfunction "1_1") (pintype "passive"))
      (node (ref "R7") (pin "1") (pinfunction "1_1") (pintype "passive"))
    )
    (net (code "50") (name "Net-(Q7-B)") (class "Default")
      (node (ref "Q7") (pin "1") (pinfunction "B_1") (pintype "passive"))
      (node (ref "R12") (pin "1") (pinfunction "1_1") (pintype "passive"))
    )
    (net (code "51") (name "Net-(Q8-G)") (class "Default")
      (node (ref "Q8") (pin "2") (pinfunction "G_2") (pintype "passive"))
      (node (ref "R21") (pin "2") (pinfunction "2_2") (pintype "passive"))
    )
    (net (code "52") (name "Net-(Q9-G)") (class "Default")
      (node (ref "Q9") (pin "2") (pinfunction "G_2") (pintype "passive"))
      (node (ref "R22") (pin "2") (pinfunction "2_2") (pintype "passive"))
    )
    (net (code "53") (name "Net-(Q10-G)") (class "Default")
      (node (ref "Q10") (pin "2") (pinfunction "G_2") (pintype "passive"))
      (node (ref "R23") (pin "2") (pinfunction "2_2") (pintype "passive"))
    )
    (net (code "54") (name "Net-(Q11-G)") (class "Default")
      (node (ref "Q11") (pin "2") (pinfunction "G_2") (pintype "passive"))
      (node (ref "R24") (pin "2") (pinfunction "2_2") (pintype "passive"))
    )
    (net (code "55") (name "Net-(Q12-Pad1)") (class "Default")
      (node (ref "Q12") (pin "1") (pinfunction "1_1") (pintype "passive"))
      (node (ref "R20") (pin "2") (pinfunction "2_2") (pintype "passive"))
      (node (ref "R25") (pin "2") (pinfunction "2_2") (pintype "passive"))
    )
    (net (code "56") (name "Net-(Q13-Pad1)") (class "Default")
      (node (ref "Q13") (pin "1") (pinfunction "1_1") (pintype "passive"))
      (node (ref "R26") (pin "2") (pinfunction "2_2") (pintype "passive"))
      (node (ref "R30") (pin "2") (pinfunction "2_2") (pintype "passive"))
    )
    (net (code "57") (name "Net-(Q13-Pad3)") (class "Default")
      (node (ref "Q13") (pin "3") (pinfunction "3_3") (pintype "passive"))
      (node (ref "R16") (pin "1") (pinfunction "1_1") (pintype "passive"))
      (node (ref "R21") (pin "1") (pinfunction "1_1") (pintype "passive"))
    )
    (net (code "58") (name "Net-(Q14-Pad1)") (class "Default")
      (node (ref "Q14") (pin "1") (pinfunction "1_1") (pintype "passive"))
      (node (ref "R27") (pin "2") (pinfunction "2_2") (pintype "passive"))
      (node (ref "R31") (pin "2") (pinfunction "2_2") (pintype "passive"))
    )
    (net (code "59") (name "Net-(Q14-Pad3)") (class "Default")
      (node (ref "Q14") (pin "3") (pinfunction "3_3") (pintype "passive"))
      (node (ref "R17") (pin "1") (pinfunction "1_1") (pintype "passive"))
      (node (ref "R22") (pin "1") (pinfunction "1_1") (pintype "passive"))
    )
    (net (code "60") (name "Net-(Q15-Pad1)") (class "Default")
      (node (ref "Q15") (pin "1") (pinfunction "1_1") (pintype "passive"))
      (node (ref "R28") (pin "2") (pinfunction "2_2") (pintype "passive"))
      (node (ref "R32") (pin "2") (pinfunction "2_2") (pintype "passive"))
    )
    (net (code "61") (name "Net-(Q15-Pad3)") (class "Default")
      (node (ref "Q15") (pin "3") (pinfunction "3_3") (pintype "passive"))
      (node (ref "R18") (pin "1") (pinfunction "1_1") (pintype "passive"))
      (node (ref "R23") (pin "1") (pinfunction "1_1") (pintype "passive"))
    )
    (net (code "62") (name "Net-(Q16-Pad1)") (class "Default")
      (node (ref "Q16") (pin "1") (pinfunction "1_1") (pintype "passive"))
      (node (ref "R29") (pin "2") (pinfunction "2_2") (pintype "passive"))
      (node (ref "R33") (pin "2") (pinfunction "2_2") (pintype "passive"))
    )
    (net (code "63") (name "Net-(Q16-Pad3)") (class "Default")
      (node (ref "Q16") (pin "3") (pinfunction "3_3") (pintype "passive"))
      (node (ref "R19") (pin "1") (pinfunction "1_1") (pintype "passive"))
      (node (ref "R24") (pin "1") (pinfunction "1_1") (pintype "passive"))
    )
    (net (code "64") (name "Net-(Q17-D)") (class "Default")
      (node (ref "F1") (pin "2") (pinfunction "2_2") (pintype "passive"))
      (node (ref "Q17") (pin "3") (pinfunction "D_3") (pintype "passive"))
    )
    (net (code "65") (name "Net-(Q17-G)") (class "Default")
      (node (ref "Q17") (pin "2") (pinfunction "G_2") (pintype "passive"))
      (node (ref "R42") (pin "2") (pinfunction "2_2") (pintype "passive"))
    )
    (net (code "66") (name "Net-(Q18-Pad1)") (class "Default")
      (node (ref "Q18") (pin "1") (pinfunction "1_1") (pintype "passive"))
      (node (ref "R44") (pin "2") (pinfunction "2_2") (pintype "passive"))
      (node (ref "R45") (pin "2") (pinfunction "2_2") (pintype "passive"))
    )
    (net (code "67") (name "Net-(Q18-Pad3)") (class "Default")
      (node (ref "Q18") (pin "3") (pinfunction "3_3") (pintype "passive"))
      (node (ref "R34") (pin "1") (pinfunction "1_1") (pintype "passive"))
      (node (ref "R42") (pin "1") (pinfunction "1_1") (pintype "passive"))
    )
    (net (code "68") (name "Net-(U1-SCL)") (class "Default")
      (node (ref "R36") (pin "1") (pinfunction "1_1") (pintype "passive"))
      (node (ref "R38") (pin "2") (pinfunction "2_2") (pintype "passive"))
      (node (ref "U1") (pin "1") (pinfunction "SCL_1") (pintype "passive"))
    )
    (net (code "69") (name "Net-(U1-SDA)") (class "Default")
      (node (ref "R37") (pin "1") (pinfunction "1_1") (pintype "passive"))
      (node (ref "R39") (pin "1") (pinfunction "1_1") (pintype "passive"))
      (node (ref "U1") (pin "6") (pinfunction "SDA_6") (pintype "passive"))
    )
    (net (code "70") (name "unconnected-(U1-ALERT-Pad3)") (class "Default")
      (node (ref "U1") (pin "3") (pinfunction "ALERT_3") (pintype "passive"))
    )
  )
)
